# A111_Pulsed_Radar_Breakout.net
KiCad netlist of a schematic drawn in EAGLE
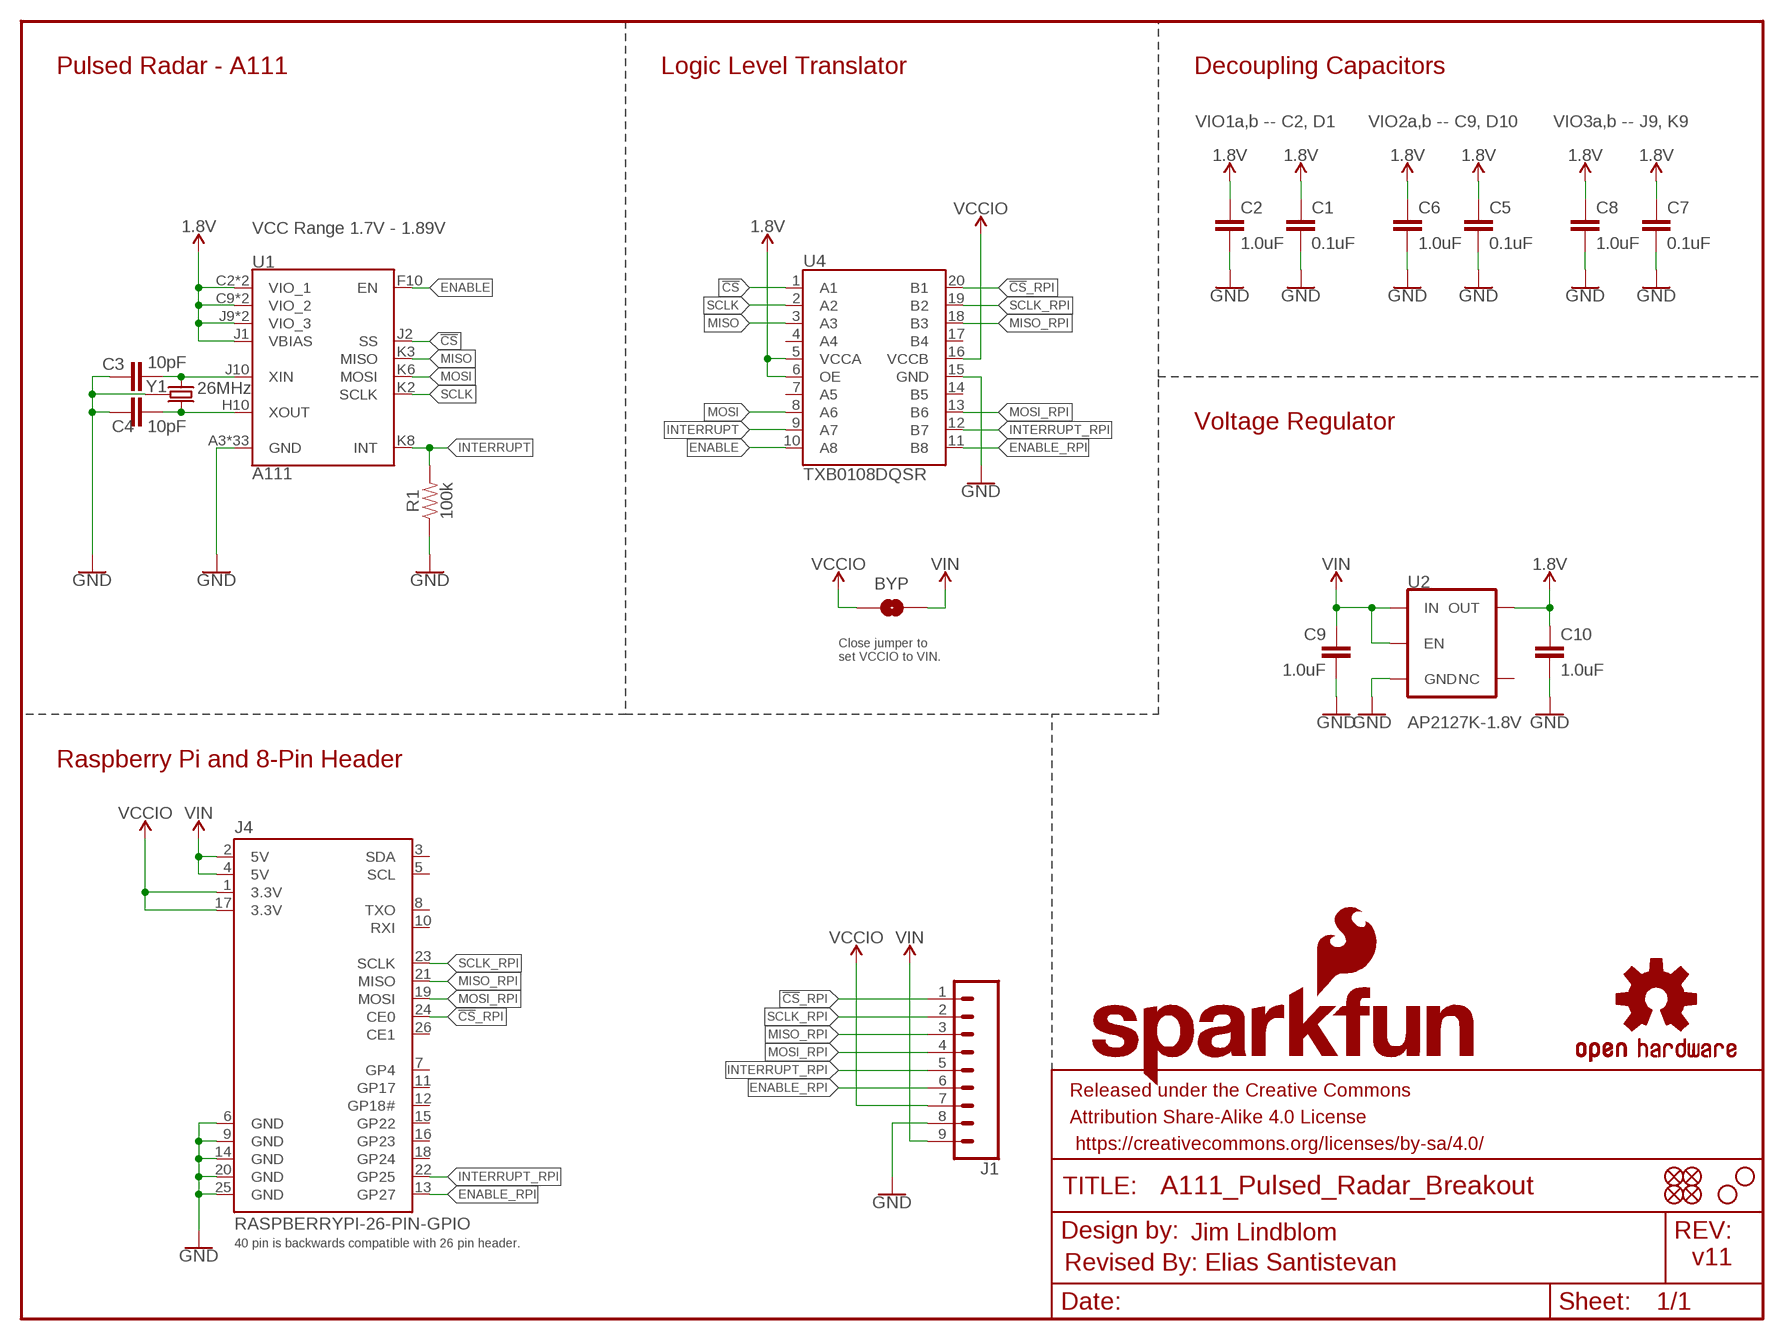
[diagram p0: schematic, sheet 1]

(export (version "E")
  (design (tool "Eeschema 10.0.6"))
  (components
    (comp (ref "BYP")
      (value "JUMPER-SMT_2_NO_SILK")
      (footprint "eagle-import:SMT-JUMPER_2_NO_SILK")
      (libsource (lib "eagle-import") (part "JUMPER-SMT_2_NO_SILK"))
    )
    (comp (ref "C1")
      (value "0.1uF")
      (footprint "eagle-import:0603")
      (libsource (lib "eagle-import") (part "0.1UF-0603-25V-(+80/-20%)"))
    )
    (comp (ref "C2")
      (value "1.0uF")
      (footprint "eagle-import:0603")
      (libsource (lib "eagle-import") (part "1.0UF-0603-16V-10%"))
    )
    (comp (ref "C3")
      (value "10pF")
      (footprint "eagle-import:0603")
      (libsource (lib "eagle-import") (part "10PF-0603-50V-5%"))
    )
    (comp (ref "C4")
      (value "10pF")
      (footprint "eagle-import:0603")
      (libsource (lib "eagle-import") (part "10PF-0603-50V-5%"))
    )
    (comp (ref "C5")
      (value "0.1uF")
      (footprint "eagle-import:0603")
      (libsource (lib "eagle-import") (part "0.1UF-0603-25V-(+80/-20%)"))
    )
    (comp (ref "C6")
      (value "1.0uF")
      (footprint "eagle-import:0603")
      (libsource (lib "eagle-import") (part "1.0UF-0603-16V-10%"))
    )
    (comp (ref "C7")
      (value "0.1uF")
      (footprint "eagle-import:0603")
      (libsource (lib "eagle-import") (part "0.1UF-0603-25V-(+80/-20%)"))
    )
    (comp (ref "C8")
      (value "1.0uF")
      (footprint "eagle-import:0603")
      (libsource (lib "eagle-import") (part "1.0UF-0603-16V-10%"))
    )
    (comp (ref "C9")
      (value "1.0uF")
      (footprint "eagle-import:0603")
      (libsource (lib "eagle-import") (part "1.0UF-0603-16V-10%"))
    )
    (comp (ref "C10")
      (value "1.0uF")
      (footprint "eagle-import:0603")
      (libsource (lib "eagle-import") (part "1.0UF-0603-16V-10%"))
    )
    (comp (ref "FD1")
      (value "FIDUCIALUFIDUCIAL")
      (footprint "eagle-import:FIDUCIAL-MICRO")
      (libsource (lib "eagle-import") (part "FIDUCIALUFIDUCIAL"))
    )
    (comp (ref "FD2")
      (value "FIDUCIALUFIDUCIAL")
      (footprint "eagle-import:FIDUCIAL-MICRO")
      (libsource (lib "eagle-import") (part "FIDUCIALUFIDUCIAL"))
    )
    (comp (ref "FD3")
      (value "FIDUCIALUFIDUCIAL")
      (footprint "eagle-import:FIDUCIAL-MICRO")
      (libsource (lib "eagle-import") (part "FIDUCIALUFIDUCIAL"))
    )
    (comp (ref "FD4")
      (value "FIDUCIALUFIDUCIAL")
      (footprint "eagle-import:FIDUCIAL-MICRO")
      (libsource (lib "eagle-import") (part "FIDUCIALUFIDUCIAL"))
    )
    (comp (ref "FRAME1")
      (value "FRAME-LETTER")
      (footprint "eagle-import:CREATIVE_COMMONS")
      (libsource (lib "eagle-import") (part "FRAME-LETTER"))
    )
    (comp (ref "H1")
      (value "STAND-OFF")
      (footprint "eagle-import:STAND-OFF")
      (libsource (lib "eagle-import") (part "STAND-OFF"))
    )
    (comp (ref "H2")
      (value "STAND-OFF")
      (footprint "eagle-import:STAND-OFF")
      (libsource (lib "eagle-import") (part "STAND-OFF"))
    )
    (comp (ref "J1")
      (value "CONN_09NO_SILK")
      (footprint "eagle-import:1X09_NO_SILK")
      (libsource (lib "eagle-import") (part "CONN_09NO_SILK"))
    )
    (comp (ref "J4")
      (value "RASPBERRYPI-26-PIN-GPIO")
      (footprint "eagle-import:2X13")
      (libsource (lib "eagle-import") (part "RASPBERRYPI-26-PIN-GPIO"))
    )
    (comp (ref "LOGO1")
      (value "SFE_LOGO_NAME_FLAME.1_INCH")
      (footprint "eagle-import:SFE_LOGO_NAME_FLAME_.1")
      (libsource (lib "eagle-import") (part "SFE_LOGO_NAME_FLAME.1_INCH"))
    )
    (comp (ref "LOGO2")
      (value "OSHW-LOGOS")
      (footprint "eagle-import:OSHW-LOGO-S")
      (libsource (lib "eagle-import") (part "OSHW-LOGOS"))
    )
    (comp (ref "R1")
      (value "100k")
      (footprint "eagle-import:0603")
      (libsource (lib "eagle-import") (part "100KOHM-0603-1/10W-1%"))
    )
    (comp (ref "U1")
      (value "A111")
      (footprint "eagle-import:A111")
      (libsource (lib "eagle-import") (part "A111"))
    )
    (comp (ref "U2")
      (value "AP2127K-1.8V")
      (footprint "eagle-import:SOT23-5")
      (libsource (lib "eagle-import") (part "V_REG_AP2127K-1.8V"))
    )
    (comp (ref "U4")
      (value "TXB0108DQSR")
      (footprint "eagle-import:UFDFN-20")
      (libsource (lib "eagle-import") (part "TXB0108"))
    )
    (comp (ref "Y1")
      (value "26MHz")
      (footprint "eagle-import:CRYSTAL-SMD-3.2X2.5MM")
      (libsource (lib "eagle-import") (part "CRYSTAL-26MHZSMD-3.2X2.5"))
    )
  )
  (nets
    (net (code "1") (name "/~{CS}") (class "Default")
      (node (ref "U1") (pin "J2") (pinfunction "SS_J2") (pintype "bidirectional"))
      (node (ref "U4") (pin "1") (pinfunction "A1_1") (pintype "bidirectional"))
    )
    (net (code "2") (name "/~{CS}_RPI") (class "Default")
      (node (ref "J1") (pin "1") (pinfunction "1_1") (pintype "passive"))
      (node (ref "J4") (pin "24") (pinfunction "CE0_24") (pintype "output"))
      (node (ref "U4") (pin "20") (pinfunction "B1_20") (pintype "bidirectional"))
    )
    (net (code "3") (name "1.8V") (class "Default")
      (node (ref "C1") (pin "1") (pinfunction "1_1") (pintype "passive"))
      (node (ref "C10") (pin "1") (pinfunction "1_1") (pintype "passive"))
      (node (ref "C2") (pin "1") (pinfunction "1_1") (pintype "passive"))
      (node (ref "C5") (pin "1") (pinfunction "1_1") (pintype "passive"))
      (node (ref "C6") (pin "1") (pinfunction "1_1") (pintype "passive"))
      (node (ref "C7") (pin "1") (pinfunction "1_1") (pintype "passive"))
      (node (ref "C8") (pin "1") (pinfunction "1_1") (pintype "passive"))
      (node (ref "U1") (pin "C2") (pinfunction "VIO_1_C2") (pintype "bidirectional"))
      (node (ref "U1") (pin "C9") (pinfunction "VIO_2_C9") (pintype "bidirectional"))
      (node (ref "U1") (pin "D1") (pinfunction "VIO_1_D1") (pintype "bidirectional"))
      (node (ref "U1") (pin "D10") (pinfunction "VIO_2_D10") (pintype "bidirectional"))
      (node (ref "U1") (pin "J1") (pinfunction "VBIAS_J1") (pintype "bidirectional"))
      (node (ref "U1") (pin "J9") (pinfunction "VIO_3_J9") (pintype "bidirectional"))
      (node (ref "U1") (pin "K9") (pinfunction "VIO_3_K9") (pintype "bidirectional"))
      (node (ref "U2") (pin "5") (pinfunction "OUT_5") (pintype "passive"))
      (node (ref "U4") (pin "5") (pinfunction "VCCA_5") (pintype "bidirectional"))
      (node (ref "U4") (pin "6") (pinfunction "OE_6") (pintype "bidirectional"))
    )
    (net (code "4") (name "ENABLE") (class "Default")
      (node (ref "U1") (pin "F10") (pinfunction "EN_F10") (pintype "bidirectional"))
      (node (ref "U4") (pin "10") (pinfunction "A8_10") (pintype "bidirectional"))
    )
    (net (code "5") (name "ENABLE_RPI") (class "Default")
      (node (ref "J1") (pin "6") (pinfunction "6_6") (pintype "passive"))
      (node (ref "J4") (pin "13") (pinfunction "GP27_13") (pintype "bidirectional"))
      (node (ref "U4") (pin "11") (pinfunction "B8_11") (pintype "bidirectional"))
    )
    (net (code "6") (name "GND") (class "Default")
      (node (ref "C1") (pin "2") (pinfunction "2_2") (pintype "passive"))
      (node (ref "C10") (pin "2") (pinfunction "2_2") (pintype "passive"))
      (node (ref "C2") (pin "2") (pinfunction "2_2") (pintype "passive"))
      (node (ref "C3") (pin "2") (pinfunction "2_2") (pintype "passive"))
      (node (ref "C4") (pin "1") (pinfunction "1_1") (pintype "passive"))
      (node (ref "C5") (pin "2") (pinfunction "2_2") (pintype "passive"))
      (node (ref "C6") (pin "2") (pinfunction "2_2") (pintype "passive"))
      (node (ref "C7") (pin "2") (pinfunction "2_2") (pintype "passive"))
      (node (ref "C8") (pin "2") (pinfunction "2_2") (pintype "passive"))
      (node (ref "C9") (pin "2") (pinfunction "2_2") (pintype "passive"))
      (node (ref "J1") (pin "8") (pinfunction "8_8") (pintype "passive"))
      (node (ref "J4") (pin "14") (pinfunction "GND_14") (pintype "power_in"))
      (node (ref "J4") (pin "20") (pinfunction "GND_20") (pintype "power_in"))
      (node (ref "J4") (pin "25") (pinfunction "GND_25") (pintype "power_in"))
      (node (ref "J4") (pin "6") (pinfunction "GND_6") (pintype "power_in"))
      (node (ref "J4") (pin "9") (pinfunction "GND_9") (pintype "power_in"))
      (node (ref "R1") (pin "1") (pinfunction "1_1") (pintype "passive"))
      (node (ref "U1") (pin "A3") (pinfunction "GND_A3") (pintype "bidirectional"))
      (node (ref "U1") (pin "A4") (pinfunction "GND_A4") (pintype "bidirectional"))
      (node (ref "U1") (pin "A5") (pinfunction "GND_A5") (pintype "bidirectional"))
      (node (ref "U1") (pin "A6") (pinfunction "GND_A6") (pintype "bidirectional"))
      (node (ref "U1") (pin "A7") (pinfunction "GND_A7") (pintype "bidirectional"))
      (node (ref "U1") (pin "A8") (pinfunction "GND_A8") (pintype "bidirectional"))
      (node (ref "U1") (pin "A9") (pinfunction "GND_A9") (pintype "bidirectional"))
      (node (ref "U1") (pin "B10") (pinfunction "GND_B10") (pintype "bidirectional"))
      (node (ref "U1") (pin "B2") (pinfunction "GND_B2") (pintype "bidirectional"))
      (node (ref "U1") (pin "B9") (pinfunction "GND_B9") (pintype "bidirectional"))
      (node (ref "U1") (pin "C1") (pinfunction "GND_C1") (pintype "bidirectional"))
      (node (ref "U1") (pin "C10") (pinfunction "GND_C10") (pintype "bidirectional"))
      (node (ref "U1") (pin "D2") (pinfunction "GND_D2") (pintype "bidirectional"))
      (node (ref "U1") (pin "D9") (pinfunction "GND_D9") (pintype "bidirectional"))
      (node (ref "U1") (pin "E1") (pinfunction "GND_E1") (pintype "bidirectional"))
      (node (ref "U1") (pin "E10") (pinfunction "GND_E10") (pintype "bidirectional"))
      (node (ref "U1") (pin "E2") (pinfunction "GND_E2") (pintype "bidirectional"))
      (node (ref "U1") (pin "E9") (pinfunction "GND_E9") (pintype "bidirectional"))
      (node (ref "U1") (pin "F1") (pinfunction "GND_F1") (pintype "bidirectional"))
      (node (ref "U1") (pin "F2") (pinfunction "GND_F2") (pintype "bidirectional"))
      (node (ref "U1") (pin "F9") (pinfunction "GND_F9") (pintype "bidirectional"))
      (node (ref "U1") (pin "G1") (pinfunction "GND_G1") (pintype "bidirectional"))
      (node (ref "U1") (pin "G10") (pinfunction "GND_G10") (pintype "bidirectional"))
      (node (ref "U1") (pin "H1") (pinfunction "GND_H1") (pintype "bidirectional"))
      (node (ref "U1") (pin "H2") (pinfunction "GND_H2") (pintype "bidirectional"))
      (node (ref "U1") (pin "H9") (pinfunction "GND_H9") (pintype "bidirectional"))
      (node (ref "U1") (pin "J3") (pinfunction "GND_J3") (pintype "bidirectional"))
      (node (ref "U1") (pin "J5") (pinfunction "GND_J5") (pintype "bidirectional"))
      (node (ref "U1") (pin "J6") (pinfunction "GND_J6") (pintype "bidirectional"))
      (node (ref "U1") (pin "J8") (pinfunction "GND_J8") (pintype "bidirectional"))
      (node (ref "U1") (pin "K4") (pinfunction "GND_K4") (pintype "bidirectional"))
      (node (ref "U1") (pin "K5") (pinfunction "GND_K5") (pintype "bidirectional"))
      (node (ref "U1") (pin "K7") (pinfunction "GND_K7") (pintype "bidirectional"))
      (node (ref "U2") (pin "2") (pinfunction "GND_2") (pintype "input"))
      (node (ref "U4") (pin "15") (pinfunction "GND_15") (pintype "bidirectional"))
      (node (ref "Y1") (pin "2") (pinfunction "GND_2") (pintype "power_in"))
      (node (ref "Y1") (pin "4") (pinfunction "GND_4") (pintype "power_in"))
    )
    (net (code "7") (name "INTERRUPT") (class "Default")
      (node (ref "R1") (pin "2") (pinfunction "2_2") (pintype "passive"))
      (node (ref "U1") (pin "K8") (pinfunction "INT_K8") (pintype "bidirectional"))
      (node (ref "U4") (pin "9") (pinfunction "A7_9") (pintype "bidirectional"))
    )
    (net (code "8") (name "INTERRUPT_RPI") (class "Default")
      (node (ref "J1") (pin "5") (pinfunction "5_5") (pintype "passive"))
      (node (ref "J4") (pin "22") (pinfunction "GP25_22") (pintype "bidirectional"))
      (node (ref "U4") (pin "12") (pinfunction "B7_12") (pintype "bidirectional"))
    )
    (net (code "9") (name "MISO") (class "Default")
      (node (ref "U1") (pin "K3") (pinfunction "MISO_K3") (pintype "bidirectional"))
      (node (ref "U4") (pin "3") (pinfunction "A3_3") (pintype "bidirectional"))
    )
    (net (code "10") (name "MISO_RPI") (class "Default")
      (node (ref "J1") (pin "3") (pinfunction "3_3") (pintype "passive"))
      (node (ref "J4") (pin "21") (pinfunction "MISO_21") (pintype "input"))
      (node (ref "U4") (pin "18") (pinfunction "B3_18") (pintype "bidirectional"))
    )
    (net (code "11") (name "MOSI") (class "Default")
      (node (ref "U1") (pin "K6") (pinfunction "MOSI_K6") (pintype "bidirectional"))
      (node (ref "U4") (pin "8") (pinfunction "A6_8") (pintype "bidirectional"))
    )
    (net (code "12") (name "MOSI_RPI") (class "Default")
      (node (ref "J1") (pin "4") (pinfunction "4_4") (pintype "passive"))
      (node (ref "J4") (pin "19") (pinfunction "MOSI_19") (pintype "output"))
      (node (ref "U4") (pin "13") (pinfunction "B6_13") (pintype "bidirectional"))
    )
    (net (code "13") (name "Net-(U1-XIN)") (class "Default")
      (node (ref "C3") (pin "1") (pinfunction "1_1") (pintype "passive"))
      (node (ref "U1") (pin "J10") (pinfunction "XIN_J10") (pintype "bidirectional"))
      (node (ref "Y1") (pin "1") (pinfunction "1_1") (pintype "passive"))
    )
    (net (code "14") (name "Net-(U1-XOUT)") (class "Default")
      (node (ref "C4") (pin "2") (pinfunction "2_2") (pintype "passive"))
      (node (ref "U1") (pin "H10") (pinfunction "XOUT_H10") (pintype "bidirectional"))
      (node (ref "Y1") (pin "3") (pinfunction "2_3") (pintype "passive"))
    )
    (net (code "15") (name "SCLK") (class "Default")
      (node (ref "U1") (pin "K2") (pinfunction "SCLK_K2") (pintype "bidirectional"))
      (node (ref "U4") (pin "2") (pinfunction "A2_2") (pintype "bidirectional"))
    )
    (net (code "16") (name "SCLK_RPI") (class "Default")
      (node (ref "J1") (pin "2") (pinfunction "2_2") (pintype "passive"))
      (node (ref "J4") (pin "23") (pinfunction "SCLK_23") (pintype "output"))
      (node (ref "U4") (pin "19") (pinfunction "B2_19") (pintype "bidirectional"))
    )
    (net (code "17") (name "VCCIO") (class "Default")
      (node (ref "BYP") (pin "1") (pinfunction "1_1") (pintype "passive"))
      (node (ref "J1") (pin "7") (pinfunction "7_7") (pintype "passive"))
      (node (ref "J4") (pin "1") (pinfunction "3.3V_1") (pintype "power_in"))
      (node (ref "J4") (pin "17") (pinfunction "3.3V_17") (pintype "power_in"))
      (node (ref "U4") (pin "16") (pinfunction "VCCB_16") (pintype "bidirectional"))
    )
    (net (code "18") (name "VIN") (class "Default")
      (node (ref "BYP") (pin "2") (pinfunction "2_2") (pintype "passive"))
      (node (ref "C9") (pin "1") (pinfunction "1_1") (pintype "passive"))
      (node (ref "J1") (pin "9") (pinfunction "9_9") (pintype "passive"))
      (node (ref "J4") (pin "2") (pinfunction "5V_2") (pintype "power_in"))
      (node (ref "J4") (pin "4") (pinfunction "5V_4") (pintype "power_in"))
      (node (ref "U2") (pin "1") (pinfunction "IN_1") (pintype "input"))
      (node (ref "U2") (pin "3") (pinfunction "EN_3") (pintype "input"))
    )
    (net (code "19") (name "unconnected-(J4-CE1-Pad26)") (class "Default")
      (node (ref "J4") (pin "26") (pinfunction "CE1_26") (pintype "output"))
    )
    (net (code "20") (name "unconnected-(J4-GP4-Pad7)") (class "Default")
      (node (ref "J4") (pin "7") (pinfunction "GP4_7") (pintype "bidirectional"))
    )
    (net (code "21") (name "unconnected-(J4-GP17-Pad11)") (class "Default")
      (node (ref "J4") (pin "11") (pinfunction "GP17_11") (pintype "bidirectional"))
    )
    (net (code "22") (name "unconnected-(J4-GP18#-Pad12)") (class "Default")
      (node (ref "J4") (pin "12") (pinfunction "GP18#_12") (pintype "bidirectional"))
    )
    (net (code "23") (name "unconnected-(J4-GP22-Pad15)") (class "Default")
      (node (ref "J4") (pin "15") (pinfunction "GP22_15") (pintype "bidirectional"))
    )
    (net (code "24") (name "unconnected-(J4-GP23-Pad16)") (class "Default")
      (node (ref "J4") (pin "16") (pinfunction "GP23_16") (pintype "bidirectional"))
    )
    (net (code "25") (name "unconnected-(J4-GP24-Pad18)") (class "Default")
      (node (ref "J4") (pin "18") (pinfunction "GP24_18") (pintype "bidirectional"))
    )
    (net (code "26") (name "unconnected-(J4-RXI-Pad10)") (class "Default")
      (node (ref "J4") (pin "10") (pinfunction "RXI_10") (pintype "input"))
    )
    (net (code "27") (name "unconnected-(J4-SCL-Pad5)") (class "Default")
      (node (ref "J4") (pin "5") (pinfunction "SCL_5") (pintype "bidirectional"))
    )
    (net (code "28") (name "unconnected-(J4-SDA-Pad3)") (class "Default")
      (node (ref "J4") (pin "3") (pinfunction "SDA_3") (pintype "bidirectional"))
    )
    (net (code "29") (name "unconnected-(J4-TXO-Pad8)") (class "Default")
      (node (ref "J4") (pin "8") (pinfunction "TXO_8") (pintype "output"))
    )
    (net (code "30") (name "unconnected-(U2-NC-Pad4)") (class "Default")
      (node (ref "U2") (pin "4") (pinfunction "NC_4") (pintype "no_connect"))
    )
    (net (code "31") (name "unconnected-(U4-A4-Pad4)") (class "Default")
      (node (ref "U4") (pin "4") (pinfunction "A4_4") (pintype "bidirectional"))
    )
    (net (code "32") (name "unconnected-(U4-A5-Pad7)") (class "Default")
      (node (ref "U4") (pin "7") (pinfunction "A5_7") (pintype "bidirectional"))
    )
    (net (code "33") (name "unconnected-(U4-B4-Pad17)") (class "Default")
      (node (ref "U4") (pin "17") (pinfunction "B4_17") (pintype "bidirectional"))
    )
    (net (code "34") (name "unconnected-(U4-B5-Pad14)") (class "Default")
      (node (ref "U4") (pin "14") (pinfunction "B5_14") (pintype "bidirectional"))
    )
  )
)
